# GPIO.net
KiCad netlist of a schematic drawn in Altium Designer
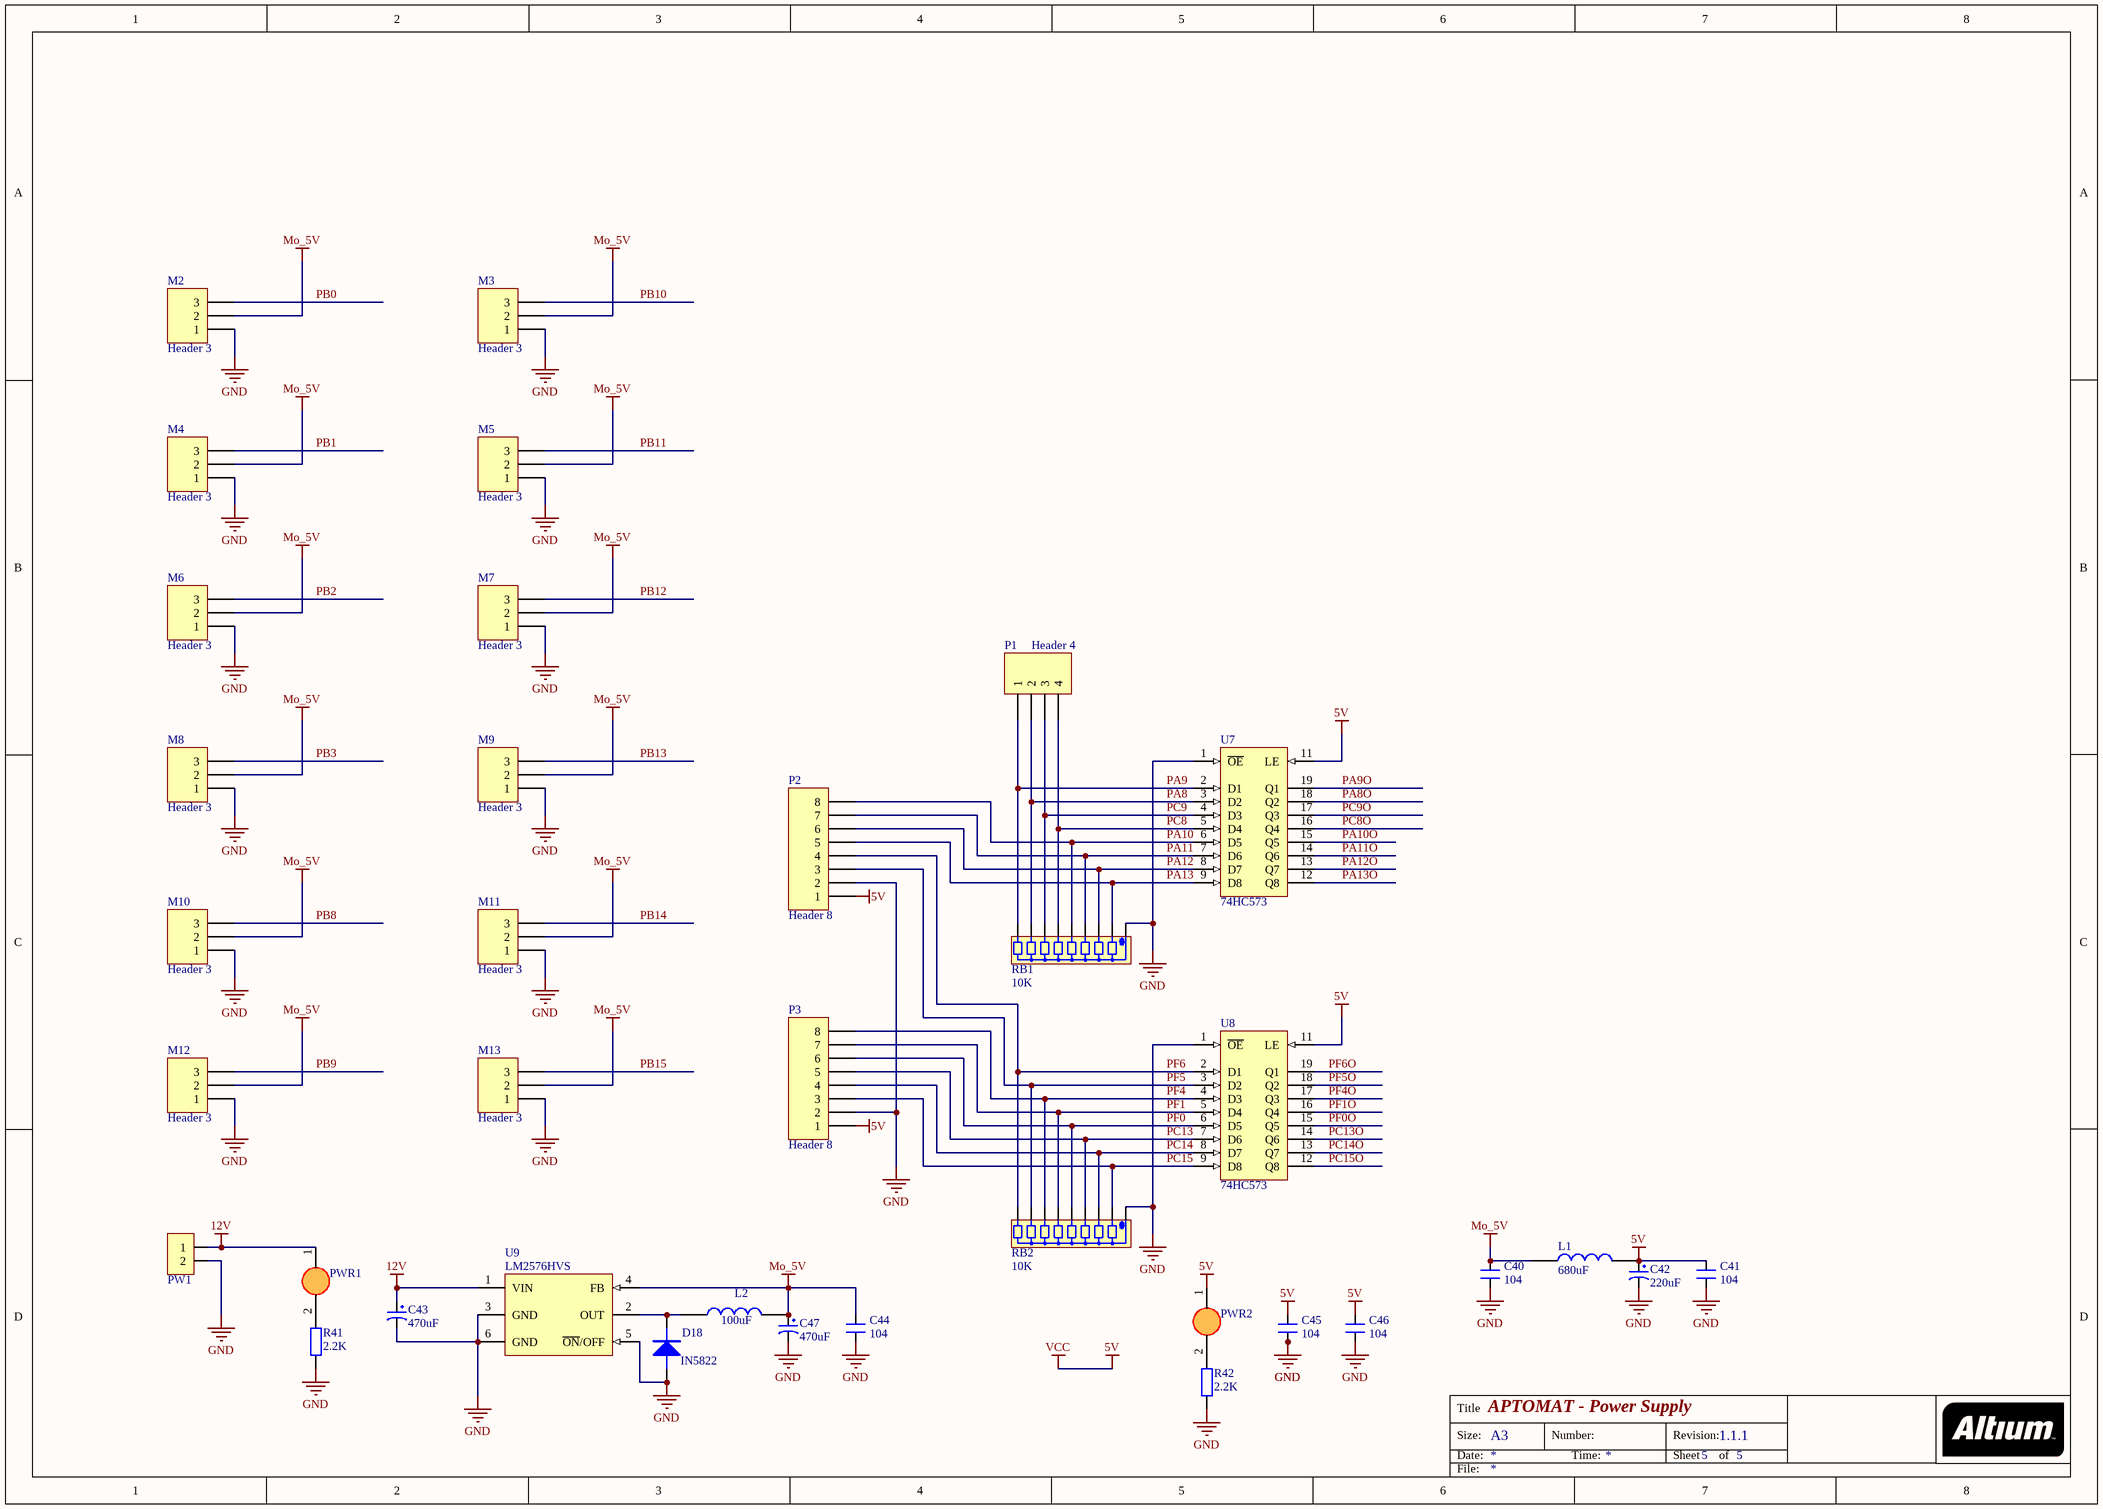
[diagram p0: GPIO.SchDoc]

(export (version "E")
  (design (tool "Eeschema 10.0.6"))
  (components
    (comp (ref "C40")
      (value "104")
      (footprint "0805_HV")
      (description "Cap SMD")
      (libsource (lib "hatcatbietbay") (part "CM"))
    )
    (comp (ref "C41")
      (value "104")
      (footprint "0805_HV")
      (description "Cap SMD")
      (libsource (lib "hatcatbietbay") (part "CM"))
    )
    (comp (ref "C42")
      (value "220uF")
      (footprint "TU_NHOM_2.5_MH")
      (description "TU_NHOM_220uF_25V_MH")
      (libsource (lib "MH_DA_THU_VIEN_16122016") (part "TU_NHOM_220uF_25V_MH"))
    )
    (comp (ref "C43")
      (value "470uF")
      (footprint "TU_NHOM_470uF_25V_MH")
      (description "TU_NHOM_470uF_25V_MH")
      (libsource (lib "MH_DA_THU_VIEN_16122016") (part "TU_NHOM_470uF_25V_MH"))
    )
    (comp (ref "C44")
      (value "104")
      (footprint "0805_HV")
      (description "Cap SMD")
      (libsource (lib "hatcatbietbay") (part "CM"))
    )
    (comp (ref "C45")
      (value "104")
      (footprint "0805_HV")
      (description "Cap SMD")
      (libsource (lib "hatcatbietbay") (part "CM"))
    )
    (comp (ref "C46")
      (value "104")
      (footprint "0805_HV")
      (description "Cap SMD")
      (libsource (lib "hatcatbietbay") (part "CM"))
    )
    (comp (ref "C47")
      (value "470uF")
      (footprint "TU_NHOM_470uF_25V_MH")
      (description "TU_NHOM_470uF_25V_MH")
      (libsource (lib "MH_DA_THU_VIEN_16122016") (part "TU_NHOM_470uF_25V_MH"))
    )
    (comp (ref "D18")
      (value "IN5822")
      (footprint "SOD123")
      (description "Diode S4 SOD123 ( 1N5819 SOD123)")
      (libsource (lib "MH_DA_THU_VIEN_16122016") (part "Diode S4 SOD123 ( 1N5819 SOD123)_MH"))
    )
    (comp (ref "L1")
      (value "680uF")
      (footprint "Inductor 4.5x5")
      (libsource (lib "MH_DA_THU_VIEN_16122016") (part "Inductor 4.5x5_MH"))
    )
    (comp (ref "L2")
      (value "100uF")
      (footprint "IND_2118-V-RC")
      (description "cuon cam")
      (libsource (lib "MH_DA_THU_VIEN_16122016") (part "Inductor Lm2576_MH"))
    )
    (comp (ref "M2")
      (value "Header 3")
      (footprint "HDR1X3")
      (description "Header, 3-Pin")
      (fields (field (name "PUBLISHER") "Altium Limited"))
      (libsource (lib "Miscellaneous Connectors") (part "Header 3"))
    )
    (comp (ref "M3")
      (value "Header 3")
      (footprint "HDR1X3")
      (description "Header, 3-Pin")
      (fields (field (name "PUBLISHER") "Altium Limited"))
      (libsource (lib "Miscellaneous Connectors") (part "Header 3"))
    )
    (comp (ref "M4")
      (value "Header 3")
      (footprint "HDR1X3")
      (description "Header, 3-Pin")
      (fields (field (name "PUBLISHER") "Altium Limited"))
      (libsource (lib "Miscellaneous Connectors") (part "Header 3"))
    )
    (comp (ref "M5")
      (value "Header 3")
      (footprint "HDR1X3")
      (description "Header, 3-Pin")
      (fields (field (name "PUBLISHER") "Altium Limited"))
      (libsource (lib "Miscellaneous Connectors") (part "Header 3"))
    )
    (comp (ref "M6")
      (value "Header 3")
      (footprint "HDR1X3")
      (description "Header, 3-Pin")
      (fields (field (name "PUBLISHER") "Altium Limited"))
      (libsource (lib "Miscellaneous Connectors") (part "Header 3"))
    )
    (comp (ref "M7")
      (value "Header 3")
      (footprint "HDR1X3")
      (description "Header, 3-Pin")
      (fields (field (name "PUBLISHER") "Altium Limited"))
      (libsource (lib "Miscellaneous Connectors") (part "Header 3"))
    )
    (comp (ref "M8")
      (value "Header 3")
      (footprint "HDR1X3")
      (description "Header, 3-Pin")
      (fields (field (name "PUBLISHER") "Altium Limited"))
      (libsource (lib "Miscellaneous Connectors") (part "Header 3"))
    )
    (comp (ref "M9")
      (value "Header 3")
      (footprint "HDR1X3")
      (description "Header, 3-Pin")
      (fields (field (name "PUBLISHER") "Altium Limited"))
      (libsource (lib "Miscellaneous Connectors") (part "Header 3"))
    )
    (comp (ref "M10")
      (value "Header 3")
      (footprint "HDR1X3")
      (description "Header, 3-Pin")
      (fields (field (name "PUBLISHER") "Altium Limited"))
      (libsource (lib "Miscellaneous Connectors") (part "Header 3"))
    )
    (comp (ref "M11")
      (value "Header 3")
      (footprint "HDR1X3")
      (description "Header, 3-Pin")
      (fields (field (name "PUBLISHER") "Altium Limited"))
      (libsource (lib "Miscellaneous Connectors") (part "Header 3"))
    )
    (comp (ref "M12")
      (value "Header 3")
      (footprint "HDR1X3")
      (description "Header, 3-Pin")
      (fields (field (name "PUBLISHER") "Altium Limited"))
      (libsource (lib "Miscellaneous Connectors") (part "Header 3"))
    )
    (comp (ref "M13")
      (value "Header 3")
      (footprint "HDR1X3")
      (description "Header, 3-Pin")
      (fields (field (name "PUBLISHER") "Altium Limited"))
      (libsource (lib "Miscellaneous Connectors") (part "Header 3"))
    )
    (comp (ref "P1")
      (value "Header 4")
      (footprint "HDR1X4")
      (description "Header, 4-Pin")
      (fields (field (name "PUBLISHER") "Altium Limited"))
      (libsource (lib "Miscellaneous Connectors") (part "Header 4"))
    )
    (comp (ref "P2")
      (value "Header 8")
      (footprint "HEADER2M_8P")
      (description "Header, 8-Pin")
      (fields (field (name "PUBLISHER") "Altium Limited"))
      (libsource (lib "Miscellaneous Connectors") (part "Header 8"))
    )
    (comp (ref "P3")
      (value "Header 8")
      (footprint "HEADER2M_8P")
      (description "Header, 8-Pin")
      (fields (field (name "PUBLISHER") "Altium Limited"))
      (libsource (lib "Miscellaneous Connectors") (part "Header 8"))
    )
    (comp (ref "PW1")
      (value "CON 2 EDG 5.08_MH")
      (footprint "CON 2 EDG 5.08")
      (description "CON 2 EDG 5.08 (xanh cong)")
      (libsource (lib "MH_DA_THU_VIEN_16122016") (part "CON 2 EDG 5.08_MH"))
    )
    (comp (ref "PWR1")
      (value "LED3")
      (footprint "LED_0805")
      (description "LED 3mm")
      (libsource (lib "MH_DA_THU_VIEN_16122016") (part "LED SMD_0805_MH"))
    )
    (comp (ref "PWR2")
      (value "LED3")
      (footprint "LED_0805")
      (description "LED 3mm")
      (libsource (lib "MH_DA_THU_VIEN_16122016") (part "LED SMD_0805_MH"))
    )
    (comp (ref "R41")
      (value "2.2K")
      (footprint "MH_DA_THU_VIEN_16122016:Tro SMD 0805")
      (description "TRO_SMD_0805_MH")
      (libsource (lib "MH_DA_THU_VIEN_16122016") (part "TRO_SMD_0805_MH"))
    )
    (comp (ref "R42")
      (value "2.2K")
      (footprint "MH_DA_THU_VIEN_16122016:Tro SMD 0805")
      (description "TRO_SMD_0805_MH")
      (libsource (lib "MH_DA_THU_VIEN_16122016") (part "TRO_SMD_0805_MH"))
    )
    (comp (ref "RB1")
      (value "TRO_BANG_A09_MH")
      (footprint "TRO_BANG_A09")
      (fields (field (name "ALTIUM_UNNAMED_1") "10K"))
      (libsource (lib "MH_DA_THU_VIEN_16122016") (part "TRO_BANG_A09_MH"))
    )
    (comp (ref "RB2")
      (value "TRO_BANG_A09_MH")
      (footprint "TRO_BANG_A09")
      (fields (field (name "ALTIUM_UNNAMED_1") "10K"))
      (libsource (lib "MH_DA_THU_VIEN_16122016") (part "TRO_BANG_A09_MH"))
    )
    (comp (ref "U7")
      (value "74HC573")
      (footprint "DIP20")
      (description "Octal D-Type Latch with 3-State Output Non-Inverting")
      (fields (field (name "COPYRIGHT BY") "VanDungEvn@Gmail.com"))
      (libsource (lib "MH_DA_THU_VIEN_16122016") (part "74HC573 DIP20 IC Flip-Flop_MH"))
    )
    (comp (ref "U8")
      (value "74HC573")
      (footprint "DIP20")
      (description "Octal D-Type Latch with 3-State Output Non-Inverting")
      (fields (field (name "COPYRIGHT BY") "VanDungEvn@Gmail.com"))
      (libsource (lib "MH_DA_THU_VIEN_16122016") (part "74HC573 DIP20 IC Flip-Flop_MH"))
    )
    (comp (ref "U9")
      (value "LM2576HVS")
      (footprint "TO263-5")
      (description "LM2576HVS-5.0V BUCK 5V 3A TO263-5 _MH")
      (fields
        (field (name "PARTNUMBER") "LM2576T-5.0")
        (field (name "MANUFACTURER") "National Semiconductor")
        (field (name "PUBLISHER") "Altium Limited")
      )
      (libsource (lib "MH_DA_THU_VIEN_16122016") (part "LM2576HVS-5.0V BUCK 5V 3A TO263-5 _MH"))
    )
  )
  (nets
    (net (code "1") (name "/PA8") (class "Default")
      (node (ref "P1") (pin "2") (pinfunction "2_2") (pintype "passive"))
      (node (ref "RB1") (pin "8") (pinfunction "8_8") (pintype "passive"))
      (node (ref "U7") (pin "3") (pinfunction "D2_3") (pintype "input"))
    )
    (net (code "2") (name "/PA8O") (class "Default")
      (node (ref "U7") (pin "18") (pinfunction "Q2_18") (pintype "tri_state"))
    )
    (net (code "3") (name "/PA9") (class "Default")
      (node (ref "P1") (pin "1") (pinfunction "1_1") (pintype "passive"))
      (node (ref "RB1") (pin "9") (pinfunction "9_9") (pintype "passive"))
      (node (ref "U7") (pin "2") (pinfunction "D1_2") (pintype "input"))
    )
    (net (code "4") (name "/PA9O") (class "Default")
      (node (ref "U7") (pin "19") (pinfunction "Q1_19") (pintype "tri_state"))
    )
    (net (code "5") (name "/PA10") (class "Default")
      (node (ref "P2") (pin "8") (pinfunction "8_8") (pintype "passive"))
      (node (ref "RB1") (pin "5") (pinfunction "5_5") (pintype "passive"))
      (node (ref "U7") (pin "6") (pinfunction "D5_6") (pintype "input"))
    )
    (net (code "6") (name "/PA10O") (class "Default")
      (node (ref "U7") (pin "15") (pinfunction "Q5_15") (pintype "tri_state"))
    )
    (net (code "7") (name "/PA11") (class "Default")
      (node (ref "P2") (pin "7") (pinfunction "7_7") (pintype "passive"))
      (node (ref "RB1") (pin "4") (pinfunction "4_4") (pintype "passive"))
      (node (ref "U7") (pin "7") (pinfunction "D6_7") (pintype "input"))
    )
    (net (code "8") (name "/PA11O") (class "Default")
      (node (ref "U7") (pin "14") (pinfunction "Q6_14") (pintype "tri_state"))
    )
    (net (code "9") (name "/PA12") (class "Default")
      (node (ref "P2") (pin "6") (pinfunction "6_6") (pintype "passive"))
      (node (ref "RB1") (pin "3") (pinfunction "3_3") (pintype "passive"))
      (node (ref "U7") (pin "8") (pinfunction "D7_8") (pintype "input"))
    )
    (net (code "10") (name "/PA12O") (class "Default")
      (node (ref "U7") (pin "13") (pinfunction "Q7_13") (pintype "tri_state"))
    )
    (net (code "11") (name "/PA13") (class "Default")
      (node (ref "P2") (pin "5") (pinfunction "5_5") (pintype "passive"))
      (node (ref "RB1") (pin "2") (pinfunction "2_2") (pintype "passive"))
      (node (ref "U7") (pin "9") (pinfunction "D8_9") (pintype "input"))
    )
    (net (code "12") (name "/PA13O") (class "Default")
      (node (ref "U7") (pin "12") (pinfunction "Q8_12") (pintype "tri_state"))
    )
    (net (code "13") (name "/PB0") (class "Default")
      (node (ref "M2") (pin "3") (pinfunction "3_3") (pintype "passive"))
    )
    (net (code "14") (name "/PB1") (class "Default")
      (node (ref "M4") (pin "3") (pinfunction "3_3") (pintype "passive"))
    )
    (net (code "15") (name "/PB2") (class "Default")
      (node (ref "M6") (pin "3") (pinfunction "3_3") (pintype "passive"))
    )
    (net (code "16") (name "/PB3") (class "Default")
      (node (ref "M8") (pin "3") (pinfunction "3_3") (pintype "passive"))
    )
    (net (code "17") (name "/PB8") (class "Default")
      (node (ref "M10") (pin "3") (pinfunction "3_3") (pintype "passive"))
    )
    (net (code "18") (name "/PB9") (class "Default")
      (node (ref "M12") (pin "3") (pinfunction "3_3") (pintype "passive"))
    )
    (net (code "19") (name "/PB10") (class "Default")
      (node (ref "M3") (pin "3") (pinfunction "3_3") (pintype "passive"))
    )
    (net (code "20") (name "/PB11") (class "Default")
      (node (ref "M5") (pin "3") (pinfunction "3_3") (pintype "passive"))
    )
    (net (code "21") (name "/PB12") (class "Default")
      (node (ref "M7") (pin "3") (pinfunction "3_3") (pintype "passive"))
    )
    (net (code "22") (name "/PB13") (class "Default")
      (node (ref "M9") (pin "3") (pinfunction "3_3") (pintype "passive"))
    )
    (net (code "23") (name "/PB14") (class "Default")
      (node (ref "M11") (pin "3") (pinfunction "3_3") (pintype "passive"))
    )
    (net (code "24") (name "/PB15") (class "Default")
      (node (ref "M13") (pin "3") (pinfunction "3_3") (pintype "passive"))
    )
    (net (code "25") (name "/PC8") (class "Default")
      (node (ref "P1") (pin "4") (pinfunction "4_4") (pintype "passive"))
      (node (ref "RB1") (pin "6") (pinfunction "6_6") (pintype "passive"))
      (node (ref "U7") (pin "5") (pinfunction "D4_5") (pintype "input"))
    )
    (net (code "26") (name "/PC8O") (class "Default")
      (node (ref "U7") (pin "16") (pinfunction "Q4_16") (pintype "tri_state"))
    )
    (net (code "27") (name "/PC9") (class "Default")
      (node (ref "P1") (pin "3") (pinfunction "3_3") (pintype "passive"))
      (node (ref "RB1") (pin "7") (pinfunction "7_7") (pintype "passive"))
      (node (ref "U7") (pin "4") (pinfunction "D3_4") (pintype "input"))
    )
    (net (code "28") (name "/PC9O") (class "Default")
      (node (ref "U7") (pin "17") (pinfunction "Q3_17") (pintype "tri_state"))
    )
    (net (code "29") (name "/PC13") (class "Default")
      (node (ref "P3") (pin "5") (pinfunction "5_5") (pintype "passive"))
      (node (ref "RB2") (pin "4") (pinfunction "4_4") (pintype "passive"))
      (node (ref "U8") (pin "7") (pinfunction "D6_7") (pintype "input"))
    )
    (net (code "30") (name "/PC13O") (class "Default")
      (node (ref "U8") (pin "14") (pinfunction "Q6_14") (pintype "tri_state"))
    )
    (net (code "31") (name "/PC14") (class "Default")
      (node (ref "P3") (pin "4") (pinfunction "4_4") (pintype "passive"))
      (node (ref "RB2") (pin "3") (pinfunction "3_3") (pintype "passive"))
      (node (ref "U8") (pin "8") (pinfunction "D7_8") (pintype "input"))
    )
    (net (code "32") (name "/PC14O") (class "Default")
      (node (ref "U8") (pin "13") (pinfunction "Q7_13") (pintype "tri_state"))
    )
    (net (code "33") (name "/PC15") (class "Default")
      (node (ref "P3") (pin "3") (pinfunction "3_3") (pintype "passive"))
      (node (ref "RB2") (pin "2") (pinfunction "2_2") (pintype "passive"))
      (node (ref "U8") (pin "9") (pinfunction "D8_9") (pintype "input"))
    )
    (net (code "34") (name "/PC15O") (class "Default")
      (node (ref "U8") (pin "12") (pinfunction "Q8_12") (pintype "tri_state"))
    )
    (net (code "35") (name "/PF0") (class "Default")
      (node (ref "P3") (pin "6") (pinfunction "6_6") (pintype "passive"))
      (node (ref "RB2") (pin "5") (pinfunction "5_5") (pintype "passive"))
      (node (ref "U8") (pin "6") (pinfunction "D5_6") (pintype "input"))
    )
    (net (code "36") (name "/PF0O") (class "Default")
      (node (ref "U8") (pin "15") (pinfunction "Q5_15") (pintype "tri_state"))
    )
    (net (code "37") (name "/PF1") (class "Default")
      (node (ref "P3") (pin "7") (pinfunction "7_7") (pintype "passive"))
      (node (ref "RB2") (pin "6") (pinfunction "6_6") (pintype "passive"))
      (node (ref "U8") (pin "5") (pinfunction "D4_5") (pintype "input"))
    )
    (net (code "38") (name "/PF1O") (class "Default")
      (node (ref "U8") (pin "16") (pinfunction "Q4_16") (pintype "tri_state"))
    )
    (net (code "39") (name "/PF4") (class "Default")
      (node (ref "P3") (pin "8") (pinfunction "8_8") (pintype "passive"))
      (node (ref "RB2") (pin "7") (pinfunction "7_7") (pintype "passive"))
      (node (ref "U8") (pin "4") (pinfunction "D3_4") (pintype "input"))
    )
    (net (code "40") (name "/PF4O") (class "Default")
      (node (ref "U8") (pin "17") (pinfunction "Q3_17") (pintype "tri_state"))
    )
    (net (code "41") (name "/PF5") (class "Default")
      (node (ref "P2") (pin "3") (pinfunction "3_3") (pintype "passive"))
      (node (ref "RB2") (pin "8") (pinfunction "8_8") (pintype "passive"))
      (node (ref "U8") (pin "3") (pinfunction "D2_3") (pintype "input"))
    )
    (net (code "42") (name "/PF5O") (class "Default")
      (node (ref "U8") (pin "18") (pinfunction "Q2_18") (pintype "tri_state"))
    )
    (net (code "43") (name "/PF6") (class "Default")
      (node (ref "P2") (pin "4") (pinfunction "4_4") (pintype "passive"))
      (node (ref "RB2") (pin "9") (pinfunction "9_9") (pintype "passive"))
      (node (ref "U8") (pin "2") (pinfunction "D1_2") (pintype "input"))
    )
    (net (code "44") (name "/PF6O") (class "Default")
      (node (ref "U8") (pin "19") (pinfunction "Q1_19") (pintype "tri_state"))
    )
    (net (code "45") (name "5V") (class "Default")
      (node (ref "C41") (pin "2") (pinfunction "2_2") (pintype "passive"))
      (node (ref "C42") (pin "1") (pinfunction "1_1") (pintype "passive"))
      (node (ref "C45") (pin "2") (pinfunction "2_2") (pintype "passive"))
      (node (ref "C46") (pin "2") (pinfunction "2_2") (pintype "passive"))
      (node (ref "L1") (pin "2") (pinfunction "2_2") (pintype "passive"))
      (node (ref "P2") (pin "1") (pinfunction "1_1") (pintype "passive"))
      (node (ref "P3") (pin "1") (pinfunction "1_1") (pintype "passive"))
      (node (ref "PWR2") (pin "1") (pinfunction "A_1") (pintype "passive"))
      (node (ref "U7") (pin "11") (pinfunction "LE_11") (pintype "input"))
      (node (ref "U7") (pin "20") (pinfunction "VCC_20") (pintype "power_in"))
      (node (ref "U8") (pin "11") (pinfunction "LE_11") (pintype "input"))
      (node (ref "U8") (pin "20") (pinfunction "VCC_20") (pintype "power_in"))
    )
    (net (code "46") (name "12V") (class "Default")
      (node (ref "C43") (pin "1") (pinfunction "1_1") (pintype "passive"))
      (node (ref "PW1") (pin "1") (pinfunction "1_1") (pintype "passive"))
      (node (ref "PWR1") (pin "1") (pinfunction "A_1") (pintype "passive"))
      (node (ref "U9") (pin "1") (pinfunction "VIN_1") (pintype "power_in"))
    )
    (net (code "47") (name "GND") (class "Default")
      (node (ref "C40") (pin "1") (pinfunction "1_1") (pintype "passive"))
      (node (ref "C41") (pin "1") (pinfunction "1_1") (pintype "passive"))
      (node (ref "C42") (pin "2") (pinfunction "2_2") (pintype "passive"))
      (node (ref "C43") (pin "2") (pinfunction "2_2") (pintype "passive"))
      (node (ref "C44") (pin "1") (pinfunction "1_1") (pintype "passive"))
      (node (ref "C45") (pin "1") (pinfunction "1_1") (pintype "passive"))
      (node (ref "C46") (pin "1") (pinfunction "1_1") (pintype "passive"))
      (node (ref "C47") (pin "2") (pinfunction "2_2") (pintype "passive"))
      (node (ref "D18") (pin "1") (pinfunction "1_1") (pintype "passive"))
      (node (ref "M10") (pin "1") (pinfunction "1_1") (pintype "passive"))
      (node (ref "M11") (pin "1") (pinfunction "1_1") (pintype "passive"))
      (node (ref "M12") (pin "1") (pinfunction "1_1") (pintype "passive"))
      (node (ref "M13") (pin "1") (pinfunction "1_1") (pintype "passive"))
      (node (ref "M2") (pin "1") (pinfunction "1_1") (pintype "passive"))
      (node (ref "M3") (pin "1") (pinfunction "1_1") (pintype "passive"))
      (node (ref "M4") (pin "1") (pinfunction "1_1") (pintype "passive"))
      (node (ref "M5") (pin "1") (pinfunction "1_1") (pintype "passive"))
      (node (ref "M6") (pin "1") (pinfunction "1_1") (pintype "passive"))
      (node (ref "M7") (pin "1") (pinfunction "1_1") (pintype "passive"))
      (node (ref "M8") (pin "1") (pinfunction "1_1") (pintype "passive"))
      (node (ref "M9") (pin "1") (pinfunction "1_1") (pintype "passive"))
      (node (ref "P2") (pin "2") (pinfunction "2_2") (pintype "passive"))
      (node (ref "P3") (pin "2") (pinfunction "2_2") (pintype "passive"))
      (node (ref "PW1") (pin "2") (pinfunction "2_2") (pintype "passive"))
      (node (ref "R41") (pin "1") (pinfunction "1_1") (pintype "passive"))
      (node (ref "R42") (pin "1") (pinfunction "1_1") (pintype "passive"))
      (node (ref "RB1") (pin "1") (pinfunction "1_1") (pintype "passive"))
      (node (ref "RB2") (pin "1") (pinfunction "1_1") (pintype "passive"))
      (node (ref "U7") (pin "1") (pinfunction "~{OE}_1") (pintype "input"))
      (node (ref "U7") (pin "10") (pinfunction "GND_10") (pintype "power_in"))
      (node (ref "U8") (pin "1") (pinfunction "~{OE}_1") (pintype "input"))
      (node (ref "U8") (pin "10") (pinfunction "GND_10") (pintype "power_in"))
      (node (ref "U9") (pin "3") (pinfunction "GND_3") (pintype "power_in"))
      (node (ref "U9") (pin "5") (pinfunction "~{ON}/OFF_5") (pintype "input"))
      (node (ref "U9") (pin "6") (pinfunction "GND_6") (pintype "passive"))
    )
    (net (code "48") (name "Mo_5V") (class "Default")
      (node (ref "C40") (pin "2") (pinfunction "2_2") (pintype "passive"))
      (node (ref "C44") (pin "2") (pinfunction "2_2") (pintype "passive"))
      (node (ref "C47") (pin "1") (pinfunction "1_1") (pintype "passive"))
      (node (ref "L1") (pin "1") (pinfunction "1_1") (pintype "passive"))
      (node (ref "L2") (pin "2") (pinfunction "2_2") (pintype "passive"))
      (node (ref "M10") (pin "2") (pinfunction "2_2") (pintype "passive"))
      (node (ref "M11") (pin "2") (pinfunction "2_2") (pintype "passive"))
      (node (ref "M12") (pin "2") (pinfunction "2_2") (pintype "passive"))
      (node (ref "M13") (pin "2") (pinfunction "2_2") (pintype "passive"))
      (node (ref "M2") (pin "2") (pinfunction "2_2") (pintype "passive"))
      (node (ref "M3") (pin "2") (pinfunction "2_2") (pintype "passive"))
      (node (ref "M4") (pin "2") (pinfunction "2_2") (pintype "passive"))
      (node (ref "M5") (pin "2") (pinfunction "2_2") (pintype "passive"))
      (node (ref "M6") (pin "2") (pinfunction "2_2") (pintype "passive"))
      (node (ref "M7") (pin "2") (pinfunction "2_2") (pintype "passive"))
      (node (ref "M8") (pin "2") (pinfunction "2_2") (pintype "passive"))
      (node (ref "M9") (pin "2") (pinfunction "2_2") (pintype "passive"))
      (node (ref "U9") (pin "4") (pinfunction "FB_4") (pintype "input"))
    )
    (net (code "49") (name "Net-(PWR1-K)") (class "Default")
      (node (ref "PWR1") (pin "2") (pinfunction "K_2") (pintype "passive"))
      (node (ref "R41") (pin "2") (pinfunction "2_2") (pintype "passive"))
    )
    (net (code "50") (name "Net-(PWR2-K)") (class "Default")
      (node (ref "PWR2") (pin "2") (pinfunction "K_2") (pintype "passive"))
      (node (ref "R42") (pin "2") (pinfunction "2_2") (pintype "passive"))
    )
    (net (code "51") (name "Net-(U9-OUT)") (class "Default")
      (node (ref "D18") (pin "2") (pinfunction "2_2") (pintype "passive"))
      (node (ref "L2") (pin "1") (pinfunction "1_1") (pintype "passive"))
      (node (ref "U9") (pin "2") (pinfunction "OUT_2") (pintype "power_in"))
    )
  )
)
